# fonte.net
KiCad netlist of a schematic drawn in EAGLE
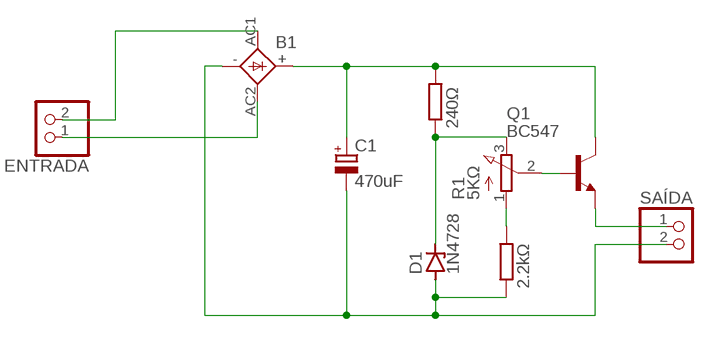
[diagram p0: schematic, sheet 1]

(export (version "E")
  (design (tool "Eeschema 10.0.6"))
  (components
    (comp (ref "B1")
      (value "1KAB")
      (footprint "eagle-import:1KAB")
      (libsource (lib "eagle-import") (part "1KAB"))
    )
    (comp (ref "C1")
      (value "470uF")
      (footprint "eagle-import:E5-10,5")
      (libsource (lib "eagle-import") (part "CPOL-EUE5-10.5"))
    )
    (comp (ref "D1")
      (value "1N4728")
      (footprint "eagle-import:DO41Z10")
      (libsource (lib "eagle-import") (part "1N4728"))
    )
    (comp (ref "ENTRADA")
      (value "PINHD-1X2")
      (footprint "eagle-import:1X02")
      (libsource (lib "eagle-import") (part "PINHD-1X2"))
    )
    (comp (ref "Q1")
      (value "BC547")
      (footprint "eagle-import:TO92")
      (libsource (lib "eagle-import") (part "BC547"))
    )
    (comp (ref "R1")
      (value "5KΩ")
      (footprint "eagle-import:3RP_1610N")
      (libsource (lib "eagle-import") (part "3RP/1610N"))
    )
    (comp (ref "R2")
      (value "2.2kΩ")
      (footprint "eagle-import:0207_10")
      (libsource (lib "eagle-import") (part "R-EU_0207/10"))
    )
    (comp (ref "R3")
      (value "240Ω")
      (footprint "eagle-import:0207_10")
      (libsource (lib "eagle-import") (part "R-EU_0207/10"))
    )
    (comp (ref "SAÍDA")
      (value "PINHD-1X2")
      (footprint "eagle-import:1X02")
      (libsource (lib "eagle-import") (part "PINHD-1X2"))
    )
  )
  (nets
    (net (code "1") (name "Net-(B1-Pad-)") (class "Default")
      (node (ref "B1") (pin "-") (pinfunction "-_-") (pintype "passive"))
      (node (ref "C1") (pin "-") (pinfunction "-_-") (pintype "passive"))
      (node (ref "D1") (pin "A") (pinfunction "A_A") (pintype "passive"))
      (node (ref "R2") (pin "1") (pinfunction "1_1") (pintype "passive"))
      (node (ref "SAÍDA") (pin "2") (pinfunction "2_2") (pintype "passive"))
    )
    (net (code "2") (name "Net-(B1-PadAC1)") (class "Default")
      (node (ref "B1") (pin "AC1") (pinfunction "AC1_AC1") (pintype "passive"))
      (node (ref "ENTRADA") (pin "2") (pinfunction "2_2") (pintype "passive"))
    )
    (net (code "3") (name "Net-(B1-PadAC2)") (class "Default")
      (node (ref "B1") (pin "AC2") (pinfunction "AC2_AC2") (pintype "passive"))
      (node (ref "ENTRADA") (pin "1") (pinfunction "1_1") (pintype "passive"))
    )
    (net (code "4") (name "Net-(Q1-B)") (class "Default")
      (node (ref "Q1") (pin "2") (pinfunction "B_2") (pintype "passive"))
      (node (ref "R1") (pin "2") (pinfunction "S_2") (pintype "passive"))
    )
    (net (code "5") (name "Net-(Q1-C)") (class "Default")
      (node (ref "B1") (pin "+") (pinfunction "+_+") (pintype "passive"))
      (node (ref "C1") (pin "+") (pinfunction "+_+") (pintype "passive"))
      (node (ref "Q1") (pin "3") (pinfunction "C_3") (pintype "passive"))
      (node (ref "R3") (pin "2") (pinfunction "2_2") (pintype "passive"))
    )
    (net (code "6") (name "Net-(Q1-E)") (class "Default")
      (node (ref "Q1") (pin "1") (pinfunction "E_1") (pintype "passive"))
      (node (ref "SAÍDA") (pin "1") (pinfunction "1_1") (pintype "passive"))
    )
    (net (code "7") (name "Net-(R1-A)") (class "Default")
      (node (ref "R1") (pin "1") (pinfunction "A_1") (pintype "passive"))
      (node (ref "R2") (pin "2") (pinfunction "2_2") (pintype "passive"))
    )
    (net (code "8") (name "Net-(R1-E)") (class "Default")
      (node (ref "D1") (pin "C") (pinfunction "C_C") (pintype "passive"))
      (node (ref "R1") (pin "3") (pinfunction "E_3") (pintype "passive"))
      (node (ref "R3") (pin "1") (pinfunction "1_1") (pintype "passive"))
    )
  )
)
